# design.net
KiCad netlist of a schematic drawn in EAGLE
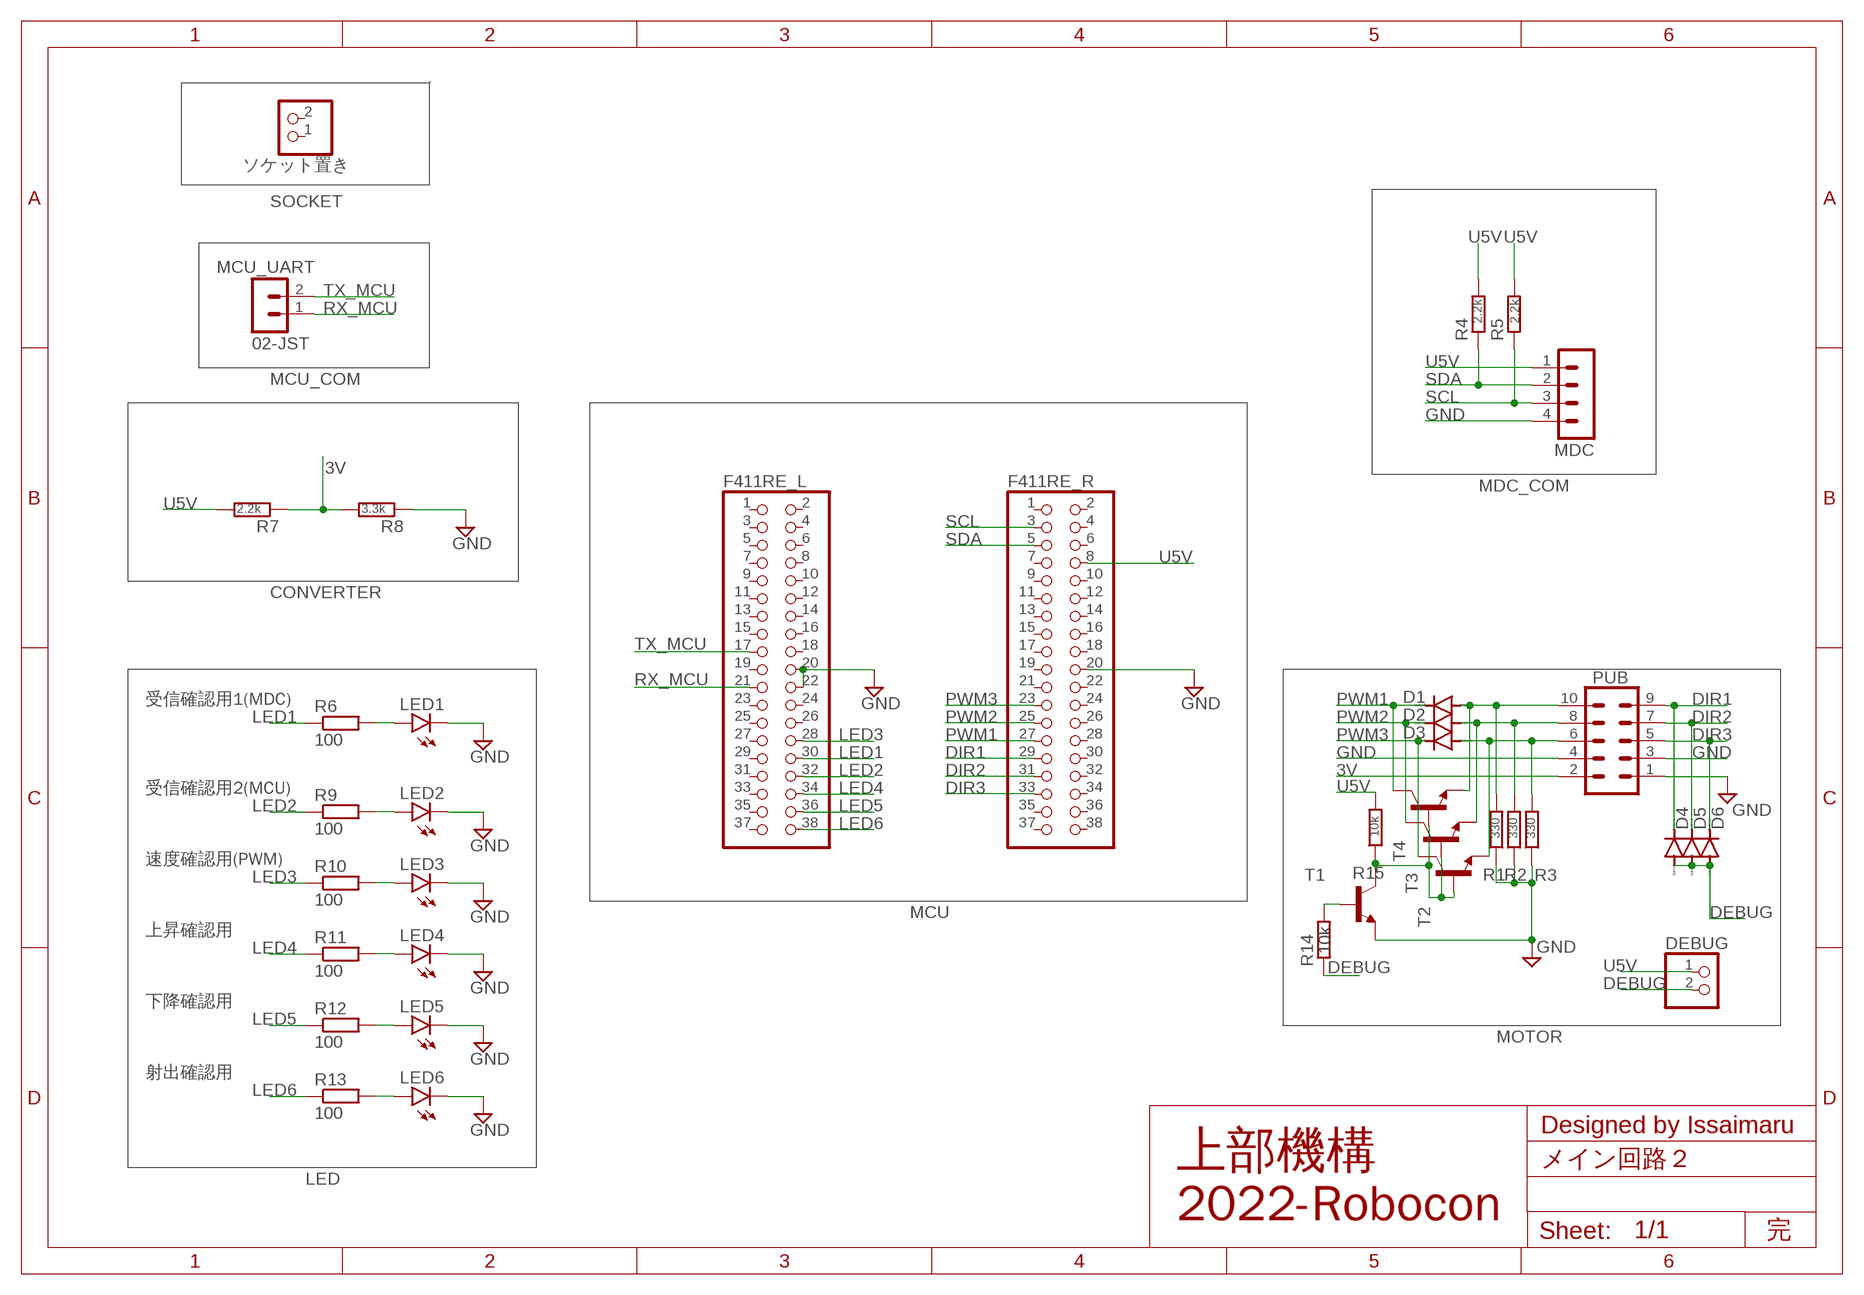
[diagram p0: schematic, sheet 1]

(export (version "E")
  (design (tool "Eeschema 10.0.6"))
  (components
    (comp (ref "D1")
      (value "1N4004")
      (footprint "eagle-import:DO41-10")
      (libsource (lib "eagle-import") (part "1N4004"))
    )
    (comp (ref "D2")
      (value "1N4004")
      (footprint "eagle-import:DO41-10")
      (libsource (lib "eagle-import") (part "1N4004"))
    )
    (comp (ref "D3")
      (value "1N4004")
      (footprint "eagle-import:DO41-10")
      (libsource (lib "eagle-import") (part "1N4004"))
    )
    (comp (ref "D4")
      (value "1N4004")
      (footprint "eagle-import:DO41-10")
      (libsource (lib "eagle-import") (part "1N4004"))
    )
    (comp (ref "D5")
      (value "1N4004")
      (footprint "eagle-import:DO41-10")
      (libsource (lib "eagle-import") (part "1N4004"))
    )
    (comp (ref "D6")
      (value "1N4004")
      (footprint "eagle-import:DO41-10")
      (libsource (lib "eagle-import") (part "1N4004"))
    )
    (comp (ref "DEBUG")
      (value "PINHD-1X2")
      (footprint "eagle-import:1X02")
      (libsource (lib "eagle-import") (part "PINHD-1X2"))
    )
    (comp (ref "F411RE_L")
      (value "PINHD-2X19")
      (footprint "eagle-import:2X19")
      (libsource (lib "eagle-import") (part "PINHD-2X19"))
    )
    (comp (ref "F411RE_R")
      (value "PINHD-2X19")
      (footprint "eagle-import:2X19")
      (libsource (lib "eagle-import") (part "PINHD-2X19"))
    )
    (comp (ref "LED1")
      (value "LED5MM")
      (footprint "eagle-import:LED5MM")
      (libsource (lib "eagle-import") (part "LED5MM"))
    )
    (comp (ref "LED2")
      (value "LED5MM")
      (footprint "eagle-import:LED5MM")
      (libsource (lib "eagle-import") (part "LED5MM"))
    )
    (comp (ref "LED3")
      (value "LED5MM")
      (footprint "eagle-import:LED5MM")
      (libsource (lib "eagle-import") (part "LED5MM"))
    )
    (comp (ref "LED4")
      (value "LED5MM")
      (footprint "eagle-import:LED5MM")
      (libsource (lib "eagle-import") (part "LED5MM"))
    )
    (comp (ref "LED5")
      (value "LED5MM")
      (footprint "eagle-import:LED5MM")
      (libsource (lib "eagle-import") (part "LED5MM"))
    )
    (comp (ref "LED6")
      (value "LED5MM")
      (footprint "eagle-import:LED5MM")
      (libsource (lib "eagle-import") (part "LED5MM"))
    )
    (comp (ref "MCU_UART")
      (value "02-JST")
      (footprint "eagle-import:B2B-XH")
      (libsource (lib "eagle-import") (part "02-JST"))
    )
    (comp (ref "MDC")
      (value "04-JST")
      (footprint "eagle-import:B4B-XH")
      (libsource (lib "eagle-import") (part "04-JST"))
    )
    (comp (ref "PUB")
      (value "ML10")
      (footprint "eagle-import:ML10")
      (libsource (lib "eagle-import") (part "ML10"))
    )
    (comp (ref "R1")
      (value "330")
      (footprint "eagle-import:0204_7")
      (libsource (lib "eagle-import") (part "R-EU_0204/7"))
    )
    (comp (ref "R2")
      (value "330")
      (footprint "eagle-import:0204_7")
      (libsource (lib "eagle-import") (part "R-EU_0204/7"))
    )
    (comp (ref "R3")
      (value "330")
      (footprint "eagle-import:0204_7")
      (libsource (lib "eagle-import") (part "R-EU_0204/7"))
    )
    (comp (ref "R4")
      (value "2.2k")
      (footprint "eagle-import:0204_7")
      (libsource (lib "eagle-import") (part "R-EU_0204/7"))
    )
    (comp (ref "R5")
      (value "2.2k")
      (footprint "eagle-import:0204_7")
      (libsource (lib "eagle-import") (part "R-EU_0204/7"))
    )
    (comp (ref "R6")
      (value "100")
      (footprint "eagle-import:0204_7")
      (libsource (lib "eagle-import") (part "R-EU_0204/7"))
    )
    (comp (ref "R7")
      (value "2.2k")
      (footprint "eagle-import:0204_7")
      (libsource (lib "eagle-import") (part "R-EU_0204/7"))
    )
    (comp (ref "R8")
      (value "3.3k")
      (footprint "eagle-import:0204_7")
      (libsource (lib "eagle-import") (part "R-EU_0204/7"))
    )
    (comp (ref "R9")
      (value "100")
      (footprint "eagle-import:0204_7")
      (libsource (lib "eagle-import") (part "R-EU_0204/7"))
    )
    (comp (ref "R10")
      (value "100")
      (footprint "eagle-import:0204_7")
      (libsource (lib "eagle-import") (part "R-EU_0204/7"))
    )
    (comp (ref "R11")
      (value "100")
      (footprint "eagle-import:0204_7")
      (libsource (lib "eagle-import") (part "R-EU_0204/7"))
    )
    (comp (ref "R12")
      (value "100")
      (footprint "eagle-import:0204_7")
      (libsource (lib "eagle-import") (part "R-EU_0204/7"))
    )
    (comp (ref "R13")
      (value "100")
      (footprint "eagle-import:0204_7")
      (libsource (lib "eagle-import") (part "R-EU_0204/7"))
    )
    (comp (ref "R14")
      (value "10k")
      (footprint "eagle-import:0204_7")
      (libsource (lib "eagle-import") (part "R-EU_0204/7"))
    )
    (comp (ref "R15")
      (value "10k")
      (footprint "eagle-import:0204_7")
      (libsource (lib "eagle-import") (part "R-EU_0204/7"))
    )
    (comp (ref "T1")
      (value "一般的なトランジスタ")
      (footprint "eagle-import:TO92-CEB")
      (libsource (lib "eagle-import") (part "一般的なトランジスタ"))
    )
    (comp (ref "T2")
      (value "一般的なトランジスタ")
      (footprint "eagle-import:TO92-CEB")
      (libsource (lib "eagle-import") (part "一般的なトランジスタ"))
    )
    (comp (ref "T3")
      (value "一般的なトランジスタ")
      (footprint "eagle-import:TO92-CEB")
      (libsource (lib "eagle-import") (part "一般的なトランジスタ"))
    )
    (comp (ref "T4")
      (value "一般的なトランジスタ")
      (footprint "eagle-import:TO92-CEB")
      (libsource (lib "eagle-import") (part "一般的なトランジスタ"))
    )
    (comp (ref "ソケット置き")
      (value "PINHD-1X2")
      (footprint "eagle-import:1X02")
      (libsource (lib "eagle-import") (part "PINHD-1X2"))
    )
  )
  (nets
    (net (code "1") (name "/3V") (class "Default")
      (node (ref "PUB") (pin "2") (pinfunction "2_2") (pintype "passive"))
      (node (ref "R7") (pin "1") (pinfunction "1_1") (pintype "passive"))
      (node (ref "R8") (pin "2") (pinfunction "2_2") (pintype "passive"))
    )
    (net (code "2") (name "/DEBUG") (class "Default")
      (node (ref "D4") (pin "A") (pinfunction "A_A") (pintype "passive"))
      (node (ref "D5") (pin "A") (pinfunction "A_A") (pintype "passive"))
      (node (ref "D6") (pin "A") (pinfunction "A_A") (pintype "passive"))
      (node (ref "DEBUG") (pin "2") (pinfunction "2_2") (pintype "passive"))
      (node (ref "R14") (pin "1") (pinfunction "1_1") (pintype "passive"))
    )
    (net (code "3") (name "/DIR1") (class "Default")
      (node (ref "D4") (pin "C") (pinfunction "C_C") (pintype "passive"))
      (node (ref "F411RE_R") (pin "29") (pinfunction "29_29") (pintype "passive"))
      (node (ref "PUB") (pin "9") (pinfunction "9_9") (pintype "passive"))
    )
    (net (code "4") (name "/DIR2") (class "Default")
      (node (ref "D5") (pin "C") (pinfunction "C_C") (pintype "passive"))
      (node (ref "F411RE_R") (pin "31") (pinfunction "31_31") (pintype "passive"))
      (node (ref "PUB") (pin "7") (pinfunction "7_7") (pintype "passive"))
    )
    (net (code "5") (name "/DIR3") (class "Default")
      (node (ref "D6") (pin "C") (pinfunction "C_C") (pintype "passive"))
      (node (ref "F411RE_R") (pin "33") (pinfunction "33_33") (pintype "passive"))
      (node (ref "PUB") (pin "5") (pinfunction "5_5") (pintype "passive"))
    )
    (net (code "6") (name "/LED1") (class "Default")
      (node (ref "F411RE_L") (pin "30") (pinfunction "30_30") (pintype "passive"))
      (node (ref "R6") (pin "1") (pinfunction "1_1") (pintype "passive"))
    )
    (net (code "7") (name "/LED2") (class "Default")
      (node (ref "F411RE_L") (pin "32") (pinfunction "32_32") (pintype "passive"))
      (node (ref "R9") (pin "1") (pinfunction "1_1") (pintype "passive"))
    )
    (net (code "8") (name "/LED3") (class "Default")
      (node (ref "F411RE_L") (pin "28") (pinfunction "28_28") (pintype "passive"))
      (node (ref "R10") (pin "1") (pinfunction "1_1") (pintype "passive"))
    )
    (net (code "9") (name "/LED4") (class "Default")
      (node (ref "F411RE_L") (pin "34") (pinfunction "34_34") (pintype "passive"))
      (node (ref "R11") (pin "1") (pinfunction "1_1") (pintype "passive"))
    )
    (net (code "10") (name "/LED5") (class "Default")
      (node (ref "F411RE_L") (pin "36") (pinfunction "36_36") (pintype "passive"))
      (node (ref "R12") (pin "1") (pinfunction "1_1") (pintype "passive"))
    )
    (net (code "11") (name "/LED6") (class "Default")
      (node (ref "F411RE_L") (pin "38") (pinfunction "38_38") (pintype "passive"))
      (node (ref "R13") (pin "1") (pinfunction "1_1") (pintype "passive"))
    )
    (net (code "12") (name "/PWM1") (class "Default")
      (node (ref "D1") (pin "C") (pinfunction "C_C") (pintype "passive"))
      (node (ref "F411RE_R") (pin "27") (pinfunction "27_27") (pintype "passive"))
      (node (ref "T4") (pin "C") (pinfunction "C_C") (pintype "passive"))
    )
    (net (code "13") (name "/PWM2") (class "Default")
      (node (ref "D2") (pin "C") (pinfunction "C_C") (pintype "passive"))
      (node (ref "F411RE_R") (pin "25") (pinfunction "25_25") (pintype "passive"))
      (node (ref "T3") (pin "C") (pinfunction "C_C") (pintype "passive"))
    )
    (net (code "14") (name "/PWM3") (class "Default")
      (node (ref "D3") (pin "C") (pinfunction "C_C") (pintype "passive"))
      (node (ref "F411RE_R") (pin "23") (pinfunction "23_23") (pintype "passive"))
      (node (ref "T2") (pin "C") (pinfunction "C_C") (pintype "passive"))
    )
    (net (code "15") (name "/RX_MCU") (class "Default")
      (node (ref "F411RE_L") (pin "21") (pinfunction "21_21") (pintype "passive"))
      (node (ref "MCU_UART") (pin "1") (pinfunction "1_1") (pintype "passive"))
    )
    (net (code "16") (name "/SCL") (class "Default")
      (node (ref "F411RE_R") (pin "3") (pinfunction "3_3") (pintype "passive"))
      (node (ref "MDC") (pin "3") (pinfunction "3_3") (pintype "passive"))
      (node (ref "R5") (pin "1") (pinfunction "1_1") (pintype "passive"))
    )
    (net (code "17") (name "/SDA") (class "Default")
      (node (ref "F411RE_R") (pin "5") (pinfunction "5_5") (pintype "passive"))
      (node (ref "MDC") (pin "2") (pinfunction "2_2") (pintype "passive"))
      (node (ref "R4") (pin "1") (pinfunction "1_1") (pintype "passive"))
    )
    (net (code "18") (name "/TX_MCU") (class "Default")
      (node (ref "F411RE_L") (pin "17") (pinfunction "17_17") (pintype "passive"))
      (node (ref "MCU_UART") (pin "2") (pinfunction "2_2") (pintype "passive"))
    )
    (net (code "19") (name "/U5V") (class "Default")
      (node (ref "DEBUG") (pin "1") (pinfunction "1_1") (pintype "passive"))
      (node (ref "F411RE_R") (pin "8") (pinfunction "8_8") (pintype "passive"))
      (node (ref "MDC") (pin "1") (pinfunction "1_1") (pintype "passive"))
      (node (ref "R15") (pin "2") (pinfunction "2_2") (pintype "passive"))
      (node (ref "R4") (pin "2") (pinfunction "2_2") (pintype "passive"))
      (node (ref "R5") (pin "2") (pinfunction "2_2") (pintype "passive"))
      (node (ref "R7") (pin "2") (pinfunction "2_2") (pintype "passive"))
    )
    (net (code "20") (name "GND") (class "Default")
      (node (ref "F411RE_L") (pin "20") (pinfunction "20_20") (pintype "passive"))
      (node (ref "F411RE_L") (pin "22") (pinfunction "22_22") (pintype "passive"))
      (node (ref "F411RE_R") (pin "20") (pinfunction "20_20") (pintype "passive"))
      (node (ref "LED1") (pin "K") (pinfunction "C_K") (pintype "passive"))
      (node (ref "LED2") (pin "K") (pinfunction "C_K") (pintype "passive"))
      (node (ref "LED3") (pin "K") (pinfunction "C_K") (pintype "passive"))
      (node (ref "LED4") (pin "K") (pinfunction "C_K") (pintype "passive"))
      (node (ref "LED5") (pin "K") (pinfunction "C_K") (pintype "passive"))
      (node (ref "LED6") (pin "K") (pinfunction "C_K") (pintype "passive"))
      (node (ref "MDC") (pin "4") (pinfunction "4_4") (pintype "passive"))
      (node (ref "PUB") (pin "1") (pinfunction "1_1") (pintype "passive"))
      (node (ref "PUB") (pin "3") (pinfunction "3_3") (pintype "passive"))
      (node (ref "PUB") (pin "4") (pinfunction "4_4") (pintype "passive"))
      (node (ref "R1") (pin "1") (pinfunction "1_1") (pintype "passive"))
      (node (ref "R2") (pin "1") (pinfunction "1_1") (pintype "passive"))
      (node (ref "R3") (pin "1") (pinfunction "1_1") (pintype "passive"))
      (node (ref "R8") (pin "1") (pinfunction "1_1") (pintype "passive"))
      (node (ref "T1") (pin "E") (pinfunction "E_E") (pintype "passive"))
    )
    (net (code "21") (name "Net-(D1-PadA)") (class "Default")
      (node (ref "D1") (pin "A") (pinfunction "A_A") (pintype "passive"))
      (node (ref "PUB") (pin "10") (pinfunction "10_10") (pintype "passive"))
      (node (ref "R1") (pin "2") (pinfunction "2_2") (pintype "passive"))
      (node (ref "T4") (pin "E") (pinfunction "E_E") (pintype "passive"))
    )
    (net (code "22") (name "Net-(D2-PadA)") (class "Default")
      (node (ref "D2") (pin "A") (pinfunction "A_A") (pintype "passive"))
      (node (ref "PUB") (pin "8") (pinfunction "8_8") (pintype "passive"))
      (node (ref "R2") (pin "2") (pinfunction "2_2") (pintype "passive"))
      (node (ref "T3") (pin "E") (pinfunction "E_E") (pintype "passive"))
    )
    (net (code "23") (name "Net-(D3-PadA)") (class "Default")
      (node (ref "D3") (pin "A") (pinfunction "A_A") (pintype "passive"))
      (node (ref "PUB") (pin "6") (pinfunction "6_6") (pintype "passive"))
      (node (ref "R3") (pin "2") (pinfunction "2_2") (pintype "passive"))
      (node (ref "T2") (pin "E") (pinfunction "E_E") (pintype "passive"))
    )
    (net (code "24") (name "Net-(LED1-PadA)") (class "Default")
      (node (ref "LED1") (pin "A") (pinfunction "A_A") (pintype "passive"))
      (node (ref "R6") (pin "2") (pinfunction "2_2") (pintype "passive"))
    )
    (net (code "25") (name "Net-(LED2-PadA)") (class "Default")
      (node (ref "LED2") (pin "A") (pinfunction "A_A") (pintype "passive"))
      (node (ref "R9") (pin "2") (pinfunction "2_2") (pintype "passive"))
    )
    (net (code "26") (name "Net-(LED3-PadA)") (class "Default")
      (node (ref "LED3") (pin "A") (pinfunction "A_A") (pintype "passive"))
      (node (ref "R10") (pin "2") (pinfunction "2_2") (pintype "passive"))
    )
    (net (code "27") (name "Net-(LED4-PadA)") (class "Default")
      (node (ref "LED4") (pin "A") (pinfunction "A_A") (pintype "passive"))
      (node (ref "R11") (pin "2") (pinfunction "2_2") (pintype "passive"))
    )
    (net (code "28") (name "Net-(LED5-PadA)") (class "Default")
      (node (ref "LED5") (pin "A") (pinfunction "A_A") (pintype "passive"))
      (node (ref "R12") (pin "2") (pinfunction "2_2") (pintype "passive"))
    )
    (net (code "29") (name "Net-(LED6-PadA)") (class "Default")
      (node (ref "LED6") (pin "A") (pinfunction "A_A") (pintype "passive"))
      (node (ref "R13") (pin "2") (pinfunction "2_2") (pintype "passive"))
    )
    (net (code "30") (name "Net-(R14-Pad2)") (class "Default")
      (node (ref "R14") (pin "2") (pinfunction "2_2") (pintype "passive"))
      (node (ref "T1") (pin "B") (pinfunction "B_B") (pintype "passive"))
    )
    (net (code "31") (name "Net-(R15-Pad1)") (class "Default")
      (node (ref "R15") (pin "1") (pinfunction "1_1") (pintype "passive"))
      (node (ref "T1") (pin "C") (pinfunction "C_C") (pintype "passive"))
      (node (ref "T2") (pin "B") (pinfunction "B_B") (pintype "passive"))
      (node (ref "T3") (pin "B") (pinfunction "B_B") (pintype "passive"))
      (node (ref "T4") (pin "B") (pinfunction "B_B") (pintype "passive"))
    )
    (net (code "32") (name "unconnected-(F411RE_L-Pad1)") (class "Default")
      (node (ref "F411RE_L") (pin "1") (pinfunction "1_1") (pintype "passive"))
    )
    (net (code "33") (name "unconnected-(F411RE_L-Pad2)") (class "Default")
      (node (ref "F411RE_L") (pin "2") (pinfunction "2_2") (pintype "passive"))
    )
    (net (code "34") (name "unconnected-(F411RE_L-Pad3)") (class "Default")
      (node (ref "F411RE_L") (pin "3") (pinfunction "3_3") (pintype "passive"))
    )
    (net (code "35") (name "unconnected-(F411RE_L-Pad4)") (class "Default")
      (node (ref "F411RE_L") (pin "4") (pinfunction "4_4") (pintype "passive"))
    )
    (net (code "36") (name "unconnected-(F411RE_L-Pad5)") (class "Default")
      (node (ref "F411RE_L") (pin "5") (pinfunction "5_5") (pintype "passive"))
    )
    (net (code "37") (name "unconnected-(F411RE_L-Pad6)") (class "Default")
      (node (ref "F411RE_L") (pin "6") (pinfunction "6_6") (pintype "passive"))
    )
    (net (code "38") (name "unconnected-(F411RE_L-Pad7)") (class "Default")
      (node (ref "F411RE_L") (pin "7") (pinfunction "7_7") (pintype "passive"))
    )
    (net (code "39") (name "unconnected-(F411RE_L-Pad8)") (class "Default")
      (node (ref "F411RE_L") (pin "8") (pinfunction "8_8") (pintype "passive"))
    )
    (net (code "40") (name "unconnected-(F411RE_L-Pad9)") (class "Default")
      (node (ref "F411RE_L") (pin "9") (pinfunction "9_9") (pintype "passive"))
    )
    (net (code "41") (name "unconnected-(F411RE_L-Pad10)") (class "Default")
      (node (ref "F411RE_L") (pin "10") (pinfunction "10_10") (pintype "passive"))
    )
    (net (code "42") (name "unconnected-(F411RE_L-Pad11)") (class "Default")
      (node (ref "F411RE_L") (pin "11") (pinfunction "11_11") (pintype "passive"))
    )
    (net (code "43") (name "unconnected-(F411RE_L-Pad12)") (class "Default")
      (node (ref "F411RE_L") (pin "12") (pinfunction "12_12") (pintype "passive"))
    )
    (net (code "44") (name "unconnected-(F411RE_L-Pad13)") (class "Default")
      (node (ref "F411RE_L") (pin "13") (pinfunction "13_13") (pintype "passive"))
    )
    (net (code "45") (name "unconnected-(F411RE_L-Pad14)") (class "Default")
      (node (ref "F411RE_L") (pin "14") (pinfunction "14_14") (pintype "passive"))
    )
    (net (code "46") (name "unconnected-(F411RE_L-Pad15)") (class "Default")
      (node (ref "F411RE_L") (pin "15") (pinfunction "15_15") (pintype "passive"))
    )
    (net (code "47") (name "unconnected-(F411RE_L-Pad16)") (class "Default")
      (node (ref "F411RE_L") (pin "16") (pinfunction "16_16") (pintype "passive"))
    )
    (net (code "48") (name "unconnected-(F411RE_L-Pad18)") (class "Default")
      (node (ref "F411RE_L") (pin "18") (pinfunction "18_18") (pintype "passive"))
    )
    (net (code "49") (name "unconnected-(F411RE_L-Pad19)") (class "Default")
      (node (ref "F411RE_L") (pin "19") (pinfunction "19_19") (pintype "passive"))
    )
    (net (code "50") (name "unconnected-(F411RE_L-Pad23)") (class "Default")
      (node (ref "F411RE_L") (pin "23") (pinfunction "23_23") (pintype "passive"))
    )
    (net (code "51") (name "unconnected-(F411RE_L-Pad24)") (class "Default")
      (node (ref "F411RE_L") (pin "24") (pinfunction "24_24") (pintype "passive"))
    )
    (net (code "52") (name "unconnected-(F411RE_L-Pad25)") (class "Default")
      (node (ref "F411RE_L") (pin "25") (pinfunction "25_25") (pintype "passive"))
    )
    (net (code "53") (name "unconnected-(F411RE_L-Pad26)") (class "Default")
      (node (ref "F411RE_L") (pin "26") (pinfunction "26_26") (pintype "passive"))
    )
    (net (code "54") (name "unconnected-(F411RE_L-Pad27)") (class "Default")
      (node (ref "F411RE_L") (pin "27") (pinfunction "27_27") (pintype "passive"))
    )
    (net (code "55") (name "unconnected-(F411RE_L-Pad29)") (class "Default")
      (node (ref "F411RE_L") (pin "29") (pinfunction "29_29") (pintype "passive"))
    )
    (net (code "56") (name "unconnected-(F411RE_L-Pad31)") (class "Default")
      (node (ref "F411RE_L") (pin "31") (pinfunction "31_31") (pintype "passive"))
    )
    (net (code "57") (name "unconnected-(F411RE_L-Pad33)") (class "Default")
      (node (ref "F411RE_L") (pin "33") (pinfunction "33_33") (pintype "passive"))
    )
    (net (code "58") (name "unconnected-(F411RE_L-Pad35)") (class "Default")
      (node (ref "F411RE_L") (pin "35") (pinfunction "35_35") (pintype "passive"))
    )
    (net (code "59") (name "unconnected-(F411RE_L-Pad37)") (class "Default")
      (node (ref "F411RE_L") (pin "37") (pinfunction "37_37") (pintype "passive"))
    )
    (net (code "60") (name "unconnected-(F411RE_R-Pad1)") (class "Default")
      (node (ref "F411RE_R") (pin "1") (pinfunction "1_1") (pintype "passive"))
    )
    (net (code "61") (name "unconnected-(F411RE_R-Pad2)") (class "Default")
      (node (ref "F411RE_R") (pin "2") (pinfunction "2_2") (pintype "passive"))
    )
    (net (code "62") (name "unconnected-(F411RE_R-Pad4)") (class "Default")
      (node (ref "F411RE_R") (pin "4") (pinfunction "4_4") (pintype "passive"))
    )
    (net (code "63") (name "unconnected-(F411RE_R-Pad6)") (class "Default")
      (node (ref "F411RE_R") (pin "6") (pinfunction "6_6") (pintype "passive"))
    )
    (net (code "64") (name "unconnected-(F411RE_R-Pad7)") (class "Default")
      (node (ref "F411RE_R") (pin "7") (pinfunction "7_7") (pintype "passive"))
    )
    (net (code "65") (name "unconnected-(F411RE_R-Pad9)") (class "Default")
      (node (ref "F411RE_R") (pin "9") (pinfunction "9_9") (pintype "passive"))
    )
    (net (code "66") (name "unconnected-(F411RE_R-Pad10)") (class "Default")
      (node (ref "F411RE_R") (pin "10") (pinfunction "10_10") (pintype "passive"))
    )
    (net (code "67") (name "unconnected-(F411RE_R-Pad11)") (class "Default")
      (node (ref "F411RE_R") (pin "11") (pinfunction "11_11") (pintype "passive"))
    )
    (net (code "68") (name "unconnected-(F411RE_R-Pad12)") (class "Default")
      (node (ref "F411RE_R") (pin "12") (pinfunction "12_12") (pintype "passive"))
    )
    (net (code "69") (name "unconnected-(F411RE_R-Pad13)") (class "Default")
      (node (ref "F411RE_R") (pin "13") (pinfunction "13_13") (pintype "passive"))
    )
    (net (code "70") (name "unconnected-(F411RE_R-Pad14)") (class "Default")
      (node (ref "F411RE_R") (pin "14") (pinfunction "14_14") (pintype "passive"))
    )
    (net (code "71") (name "unconnected-(F411RE_R-Pad15)") (class "Default")
      (node (ref "F411RE_R") (pin "15") (pinfunction "15_15") (pintype "passive"))
    )
    (net (code "72") (name "unconnected-(F411RE_R-Pad16)") (class "Default")
      (node (ref "F411RE_R") (pin "16") (pinfunction "16_16") (pintype "passive"))
    )
    (net (code "73") (name "unconnected-(F411RE_R-Pad17)") (class "Default")
      (node (ref "F411RE_R") (pin "17") (pinfunction "17_17") (pintype "passive"))
    )
    (net (code "74") (name "unconnected-(F411RE_R-Pad18)") (class "Default")
      (node (ref "F411RE_R") (pin "18") (pinfunction "18_18") (pintype "passive"))
    )
    (net (code "75") (name "unconnected-(F411RE_R-Pad19)") (class "Default")
      (node (ref "F411RE_R") (pin "19") (pinfunction "19_19") (pintype "passive"))
    )
    (net (code "76") (name "unconnected-(F411RE_R-Pad21)") (class "Default")
      (node (ref "F411RE_R") (pin "21") (pinfunction "21_21") (pintype "passive"))
    )
    (net (code "77") (name "unconnected-(F411RE_R-Pad22)") (class "Default")
      (node (ref "F411RE_R") (pin "22") (pinfunction "22_22") (pintype "passive"))
    )
    (net (code "78") (name "unconnected-(F411RE_R-Pad24)") (class "Default")
      (node (ref "F411RE_R") (pin "24") (pinfunction "24_24") (pintype "passive"))
    )
    (net (code "79") (name "unconnected-(F411RE_R-Pad26)") (class "Default")
      (node (ref "F411RE_R") (pin "26") (pinfunction "26_26") (pintype "passive"))
    )
    (net (code "80") (name "unconnected-(F411RE_R-Pad28)") (class "Default")
      (node (ref "F411RE_R") (pin "28") (pinfunction "28_28") (pintype "passive"))
    )
    (net (code "81") (name "unconnected-(F411RE_R-Pad30)") (class "Default")
      (node (ref "F411RE_R") (pin "30") (pinfunction "30_30") (pintype "passive"))
    )
    (net (code "82") (name "unconnected-(F411RE_R-Pad32)") (class "Default")
      (node (ref "F411RE_R") (pin "32") (pinfunction "32_32") (pintype "passive"))
    )
    (net (code "83") (name "unconnected-(F411RE_R-Pad34)") (class "Default")
      (node (ref "F411RE_R") (pin "34") (pinfunction "34_34") (pintype "passive"))
    )
    (net (code "84") (name "unconnected-(F411RE_R-Pad35)") (class "Default")
      (node (ref "F411RE_R") (pin "35") (pinfunction "35_35") (pintype "passive"))
    )
    (net (code "85") (name "unconnected-(F411RE_R-Pad36)") (class "Default")
      (node (ref "F411RE_R") (pin "36") (pinfunction "36_36") (pintype "passive"))
    )
    (net (code "86") (name "unconnected-(F411RE_R-Pad37)") (class "Default")
      (node (ref "F411RE_R") (pin "37") (pinfunction "37_37") (pintype "passive"))
    )
    (net (code "87") (name "unconnected-(F411RE_R-Pad38)") (class "Default")
      (node (ref "F411RE_R") (pin "38") (pinfunction "38_38") (pintype "passive"))
    )
    (net (code "88") (name "unconnected-(ソケット置き-Pad1)") (class "Default")
      (node (ref "ソケット置き") (pin "1") (pinfunction "1_1") (pintype "passive"))
    )
    (net (code "89") (name "unconnected-(ソケット置き-Pad2)") (class "Default")
      (node (ref "ソケット置き") (pin "2") (pinfunction "2_2") (pintype "passive"))
    )
  )
)
